# controller.net
KiCad netlist of a schematic drawn in EAGLE
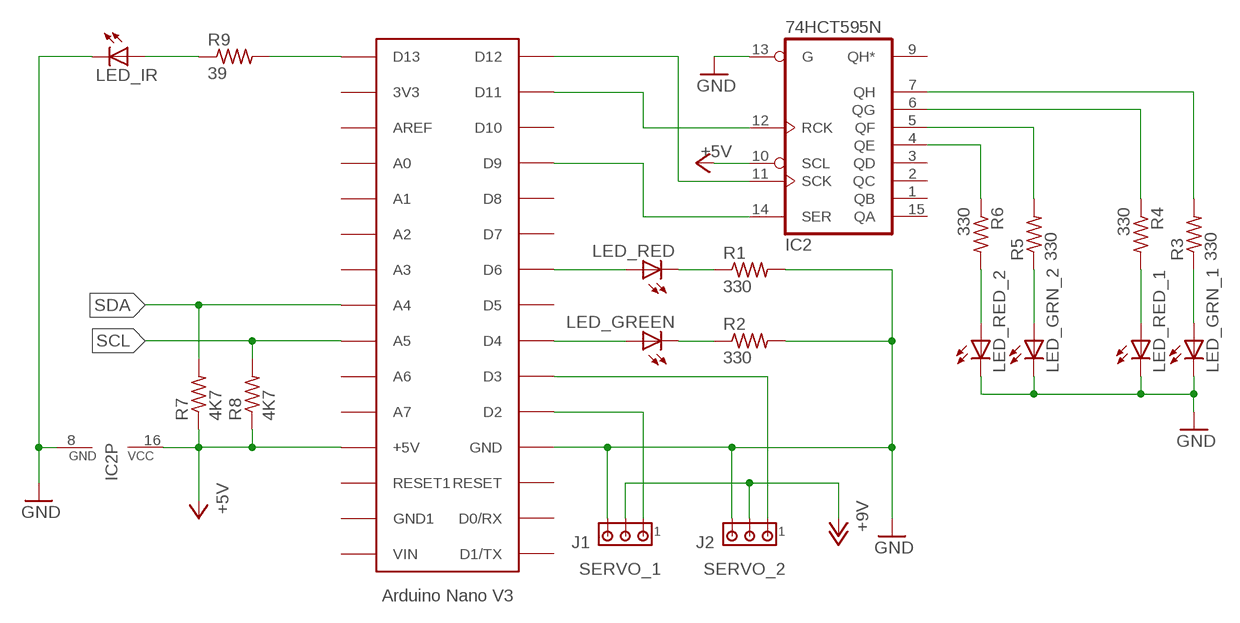
[diagram p0: schematic, sheet 1]

(export (version "E")
  (design (tool "Eeschema 10.0.6"))
  (components
    (comp (ref "IC2")
      (value "74HCT595N")
      (footprint "eagle-import:DIL16")
      (libsource (lib "eagle-import") (part "74595NHCT"))
    )
    (comp (ref "J1")
      (value "SERVO_1")
      (footprint "eagle-import:10X03MTA")
      (libsource (lib "eagle-import") (part "MTA03-100"))
    )
    (comp (ref "J2")
      (value "SERVO_2")
      (footprint "eagle-import:10X03MTA")
      (libsource (lib "eagle-import") (part "MTA03-100"))
    )
    (comp (ref "LED_GREEN")
      (value "LED5MM")
      (footprint "eagle-import:LED5MM")
      (libsource (lib "eagle-import") (part "LED5MM"))
    )
    (comp (ref "LED_GRN_1")
      (value "LED5MM")
      (footprint "eagle-import:LED5MM")
      (libsource (lib "eagle-import") (part "LED5MM"))
    )
    (comp (ref "LED_GRN_2")
      (value "LED5MM")
      (footprint "eagle-import:LED5MM")
      (libsource (lib "eagle-import") (part "LED5MM"))
    )
    (comp (ref "LED_IR")
      (value "LED5MM")
      (footprint "eagle-import:LED5MM")
      (libsource (lib "eagle-import") (part "LED5MM"))
    )
    (comp (ref "LED_RED")
      (value "LED5MM")
      (footprint "eagle-import:LED5MM")
      (libsource (lib "eagle-import") (part "LED5MM"))
    )
    (comp (ref "LED_RED_1")
      (value "LED5MM")
      (footprint "eagle-import:LED5MM")
      (libsource (lib "eagle-import") (part "LED5MM"))
    )
    (comp (ref "LED_RED_2")
      (value "LED5MM")
      (footprint "eagle-import:LED5MM")
      (libsource (lib "eagle-import") (part "LED5MM"))
    )
    (comp (ref "R1")
      (value "330")
      (footprint "eagle-import:0207_10")
      (libsource (lib "eagle-import") (part "R-US_0207/10"))
    )
    (comp (ref "R2")
      (value "330")
      (footprint "eagle-import:0207_10")
      (libsource (lib "eagle-import") (part "R-US_0207/10"))
    )
    (comp (ref "R3")
      (value "330")
      (footprint "eagle-import:0207_10")
      (libsource (lib "eagle-import") (part "R-US_0207/10"))
    )
    (comp (ref "R4")
      (value "330")
      (footprint "eagle-import:0207_10")
      (libsource (lib "eagle-import") (part "R-US_0207/10"))
    )
    (comp (ref "R5")
      (value "330")
      (footprint "eagle-import:0207_10")
      (libsource (lib "eagle-import") (part "R-US_0207/10"))
    )
    (comp (ref "R6")
      (value "330")
      (footprint "eagle-import:0207_10")
      (libsource (lib "eagle-import") (part "R-US_0207/10"))
    )
    (comp (ref "R7")
      (value "4K7")
      (footprint "eagle-import:0207_10")
      (libsource (lib "eagle-import") (part "R-US_0207/10"))
    )
    (comp (ref "R8")
      (value "4K7")
      (footprint "eagle-import:0207_10")
      (libsource (lib "eagle-import") (part "R-US_0207/10"))
    )
    (comp (ref "R9")
      (value "39")
      (footprint "eagle-import:0207_10")
      (libsource (lib "eagle-import") (part "R-US_0207/10"))
    )
    (comp (ref "U$1")
      (value "ARDUINONANO")
      (footprint "eagle-import:PDIP-32")
      (libsource (lib "eagle-import") (part "ARDUINONANO"))
    )
  )
  (nets
    (net (code "1") (name "+5V") (class "Default")
      (node (ref "IC2") (pin "10") (pinfunction "SCL_10") (pintype "input"))
      (node (ref "IC2") (pin "16") (pinfunction "VCC_16") (pintype "power_in"))
      (node (ref "R7") (pin "1") (pinfunction "1_1") (pintype "passive"))
      (node (ref "R8") (pin "1") (pinfunction "1_1") (pintype "passive"))
      (node (ref "U$1") (pin "+5V") (pinfunction "+5V_+5V") (pintype "bidirectional"))
    )
    (net (code "2") (name "+9V") (class "Default")
      (node (ref "J1") (pin "2") (pinfunction "2_2") (pintype "passive"))
      (node (ref "J2") (pin "2") (pinfunction "2_2") (pintype "passive"))
    )
    (net (code "3") (name "GND") (class "Default")
      (node (ref "IC2") (pin "13") (pinfunction "G_13") (pintype "input"))
      (node (ref "IC2") (pin "8") (pinfunction "GND_8") (pintype "power_in"))
      (node (ref "J1") (pin "3") (pinfunction "3_3") (pintype "passive"))
      (node (ref "J2") (pin "3") (pinfunction "3_3") (pintype "passive"))
      (node (ref "LED_GRN_1") (pin "K") (pinfunction "C_K") (pintype "passive"))
      (node (ref "LED_GRN_2") (pin "K") (pinfunction "C_K") (pintype "passive"))
      (node (ref "LED_IR") (pin "K") (pinfunction "C_K") (pintype "passive"))
      (node (ref "LED_RED_1") (pin "K") (pinfunction "C_K") (pintype "passive"))
      (node (ref "LED_RED_2") (pin "K") (pinfunction "C_K") (pintype "passive"))
      (node (ref "R1") (pin "2") (pinfunction "2_2") (pintype "passive"))
      (node (ref "R2") (pin "2") (pinfunction "2_2") (pintype "passive"))
      (node (ref "U$1") (pin "GND") (pinfunction "GND_GND") (pintype "bidirectional"))
    )
    (net (code "4") (name "Net-(IC2A-QE)") (class "Default")
      (node (ref "IC2") (pin "4") (pinfunction "QE_4") (pintype "tri_state"))
      (node (ref "R6") (pin "1") (pinfunction "1_1") (pintype "passive"))
    )
    (net (code "5") (name "Net-(IC2A-QF)") (class "Default")
      (node (ref "IC2") (pin "5") (pinfunction "QF_5") (pintype "tri_state"))
      (node (ref "R5") (pin "2") (pinfunction "2_2") (pintype "passive"))
    )
    (net (code "6") (name "Net-(IC2A-QG)") (class "Default")
      (node (ref "IC2") (pin "6") (pinfunction "QG_6") (pintype "tri_state"))
      (node (ref "R4") (pin "1") (pinfunction "1_1") (pintype "passive"))
    )
    (net (code "7") (name "Net-(IC2A-QH)") (class "Default")
      (node (ref "IC2") (pin "7") (pinfunction "QH_7") (pintype "tri_state"))
      (node (ref "R3") (pin "2") (pinfunction "2_2") (pintype "passive"))
    )
    (net (code "8") (name "Net-(IC2A-RCK)") (class "Default")
      (node (ref "IC2") (pin "12") (pinfunction "RCK_12") (pintype "input"))
      (node (ref "U$1") (pin "D11") (pinfunction "D11_D11") (pintype "bidirectional"))
    )
    (net (code "9") (name "Net-(IC2A-SCK)") (class "Default")
      (node (ref "IC2") (pin "11") (pinfunction "SCK_11") (pintype "input"))
      (node (ref "U$1") (pin "D12") (pinfunction "D12_D12") (pintype "bidirectional"))
    )
    (net (code "10") (name "Net-(IC2A-SER)") (class "Default")
      (node (ref "IC2") (pin "14") (pinfunction "SER_14") (pintype "input"))
      (node (ref "U$1") (pin "D9") (pinfunction "D9_D9") (pintype "bidirectional"))
    )
    (net (code "11") (name "Net-(J1-Pad1)") (class "Default")
      (node (ref "J1") (pin "1") (pinfunction "1_1") (pintype "passive"))
      (node (ref "U$1") (pin "D2") (pinfunction "D2_D2") (pintype "bidirectional"))
    )
    (net (code "12") (name "Net-(J2-Pad1)") (class "Default")
      (node (ref "J2") (pin "1") (pinfunction "1_1") (pintype "passive"))
      (node (ref "U$1") (pin "D3") (pinfunction "D3_D3") (pintype "bidirectional"))
    )
    (net (code "13") (name "Net-(LED_GREEN-C)") (class "Default")
      (node (ref "LED_GREEN") (pin "K") (pinfunction "C_K") (pintype "passive"))
      (node (ref "R2") (pin "1") (pinfunction "1_1") (pintype "passive"))
    )
    (net (code "14") (name "Net-(LED_GREEN-PadA)") (class "Default")
      (node (ref "LED_GREEN") (pin "A") (pinfunction "A_A") (pintype "passive"))
      (node (ref "U$1") (pin "D4") (pinfunction "D4_D4") (pintype "bidirectional"))
    )
    (net (code "15") (name "Net-(LED_GRN_1-PadA)") (class "Default")
      (node (ref "LED_GRN_1") (pin "A") (pinfunction "A_A") (pintype "passive"))
      (node (ref "R3") (pin "1") (pinfunction "1_1") (pintype "passive"))
    )
    (net (code "16") (name "Net-(LED_GRN_2-PadA)") (class "Default")
      (node (ref "LED_GRN_2") (pin "A") (pinfunction "A_A") (pintype "passive"))
      (node (ref "R5") (pin "1") (pinfunction "1_1") (pintype "passive"))
    )
    (net (code "17") (name "Net-(LED_IR-PadA)") (class "Default")
      (node (ref "LED_IR") (pin "A") (pinfunction "A_A") (pintype "passive"))
      (node (ref "R9") (pin "1") (pinfunction "1_1") (pintype "passive"))
    )
    (net (code "18") (name "Net-(LED_RED-C)") (class "Default")
      (node (ref "LED_RED") (pin "K") (pinfunction "C_K") (pintype "passive"))
      (node (ref "R1") (pin "1") (pinfunction "1_1") (pintype "passive"))
    )
    (net (code "19") (name "Net-(LED_RED-PadA)") (class "Default")
      (node (ref "LED_RED") (pin "A") (pinfunction "A_A") (pintype "passive"))
      (node (ref "U$1") (pin "D6") (pinfunction "D6_D6") (pintype "bidirectional"))
    )
    (net (code "20") (name "Net-(LED_RED_1-PadA)") (class "Default")
      (node (ref "LED_RED_1") (pin "A") (pinfunction "A_A") (pintype "passive"))
      (node (ref "R4") (pin "2") (pinfunction "2_2") (pintype "passive"))
    )
    (net (code "21") (name "Net-(LED_RED_2-PadA)") (class "Default")
      (node (ref "LED_RED_2") (pin "A") (pinfunction "A_A") (pintype "passive"))
      (node (ref "R6") (pin "2") (pinfunction "2_2") (pintype "passive"))
    )
    (net (code "22") (name "Net-(R9-Pad2)") (class "Default")
      (node (ref "R9") (pin "2") (pinfunction "2_2") (pintype "passive"))
      (node (ref "U$1") (pin "D13") (pinfunction "D13_D13") (pintype "bidirectional"))
    )
    (net (code "23") (name "SCL") (class "Default")
      (node (ref "R8") (pin "2") (pinfunction "2_2") (pintype "passive"))
      (node (ref "U$1") (pin "A2") (pinfunction "A5_A2") (pintype "bidirectional"))
    )
    (net (code "24") (name "SDA") (class "Default")
      (node (ref "R7") (pin "2") (pinfunction "2_2") (pintype "passive"))
      (node (ref "U$1") (pin "A3") (pinfunction "A4_A3") (pintype "bidirectional"))
    )
    (net (code "25") (name "unconnected-(IC2A-QA-Pad15)") (class "Default")
      (node (ref "IC2") (pin "15") (pinfunction "QA_15") (pintype "tri_state"))
    )
    (net (code "26") (name "unconnected-(IC2A-QB-Pad1)") (class "Default")
      (node (ref "IC2") (pin "1") (pinfunction "QB_1") (pintype "tri_state"))
    )
    (net (code "27") (name "unconnected-(IC2A-QC-Pad2)") (class "Default")
      (node (ref "IC2") (pin "2") (pinfunction "QC_2") (pintype "tri_state"))
    )
    (net (code "28") (name "unconnected-(IC2A-QD-Pad3)") (class "Default")
      (node (ref "IC2") (pin "3") (pinfunction "QD_3") (pintype "tri_state"))
    )
    (net (code "29") (name "unconnected-(IC2A-QH*-Pad9)") (class "Default")
      (node (ref "IC2") (pin "9") (pinfunction "QH*_9") (pintype "tri_state"))
    )
    (net (code "30") (name "unconnected-(U$1-A0-PadA7)") (class "Default")
      (node (ref "U$1") (pin "A7") (pinfunction "A0_A7") (pintype "bidirectional"))
    )
    (net (code "31") (name "unconnected-(U$1-A1-PadA6)") (class "Default")
      (node (ref "U$1") (pin "A6") (pinfunction "A1_A6") (pintype "bidirectional"))
    )
    (net (code "32") (name "unconnected-(U$1-A2-PadA5)") (class "Default")
      (node (ref "U$1") (pin "A5") (pinfunction "A2_A5") (pintype "bidirectional"))
    )
    (net (code "33") (name "unconnected-(U$1-A3-PadA4)") (class "Default")
      (node (ref "U$1") (pin "A4") (pinfunction "A3_A4") (pintype "bidirectional"))
    )
    (net (code "34") (name "unconnected-(U$1-A6-PadA1)") (class "Default")
      (node (ref "U$1") (pin "A1") (pinfunction "A6_A1") (pintype "bidirectional"))
    )
    (net (code "35") (name "unconnected-(U$1-A7-PadA0)") (class "Default")
      (node (ref "U$1") (pin "A0") (pinfunction "A7_A0") (pintype "bidirectional"))
    )
    (net (code "36") (name "unconnected-(U$1-Pad3V3)") (class "Default")
      (node (ref "U$1") (pin "3V3") (pinfunction "3V3_3V3") (pintype "bidirectional"))
    )
    (net (code "37") (name "unconnected-(U$1-PadAREF)") (class "Default")
      (node (ref "U$1") (pin "AREF") (pinfunction "AREF_AREF") (pintype "bidirectional"))
    )
    (net (code "38") (name "unconnected-(U$1-PadD0{slash}RX)") (class "Default")
      (node (ref "U$1") (pin "D0/RX") (pinfunction "D0/RX_D0/RX") (pintype "bidirectional"))
    )
    (net (code "39") (name "unconnected-(U$1-PadD1{slash}TX)") (class "Default")
      (node (ref "U$1") (pin "D1/TX") (pinfunction "D1/TX_D1/TX") (pintype "bidirectional"))
    )
    (net (code "40") (name "unconnected-(U$1-PadD5)") (class "Default")
      (node (ref "U$1") (pin "D5") (pinfunction "D5_D5") (pintype "bidirectional"))
    )
    (net (code "41") (name "unconnected-(U$1-PadD7)") (class "Default")
      (node (ref "U$1") (pin "D7") (pinfunction "D7_D7") (pintype "bidirectional"))
    )
    (net (code "42") (name "unconnected-(U$1-PadD8)") (class "Default")
      (node (ref "U$1") (pin "D8") (pinfunction "D8_D8") (pintype "bidirectional"))
    )
    (net (code "43") (name "unconnected-(U$1-PadD10)") (class "Default")
      (node (ref "U$1") (pin "D10") (pinfunction "D10_D10") (pintype "bidirectional"))
    )
    (net (code "44") (name "unconnected-(U$1-PadGND1)") (class "Default")
      (node (ref "U$1") (pin "GND1") (pinfunction "GND1_GND1") (pintype "bidirectional"))
    )
    (net (code "45") (name "unconnected-(U$1-PadRESET)") (class "Default")
      (node (ref "U$1") (pin "RESET") (pinfunction "RESET_RESET") (pintype "bidirectional"))
    )
    (net (code "46") (name "unconnected-(U$1-PadRESET1)") (class "Default")
      (node (ref "U$1") (pin "RESET1") (pinfunction "RESET1_RESET1") (pintype "bidirectional"))
    )
    (net (code "47") (name "unconnected-(U$1-PadVIN)") (class "Default")
      (node (ref "U$1") (pin "VIN") (pinfunction "VIN_VIN") (pintype "bidirectional"))
    )
  )
)
